# Motherboard_V2.net
KiCad netlist of a schematic drawn in EAGLE
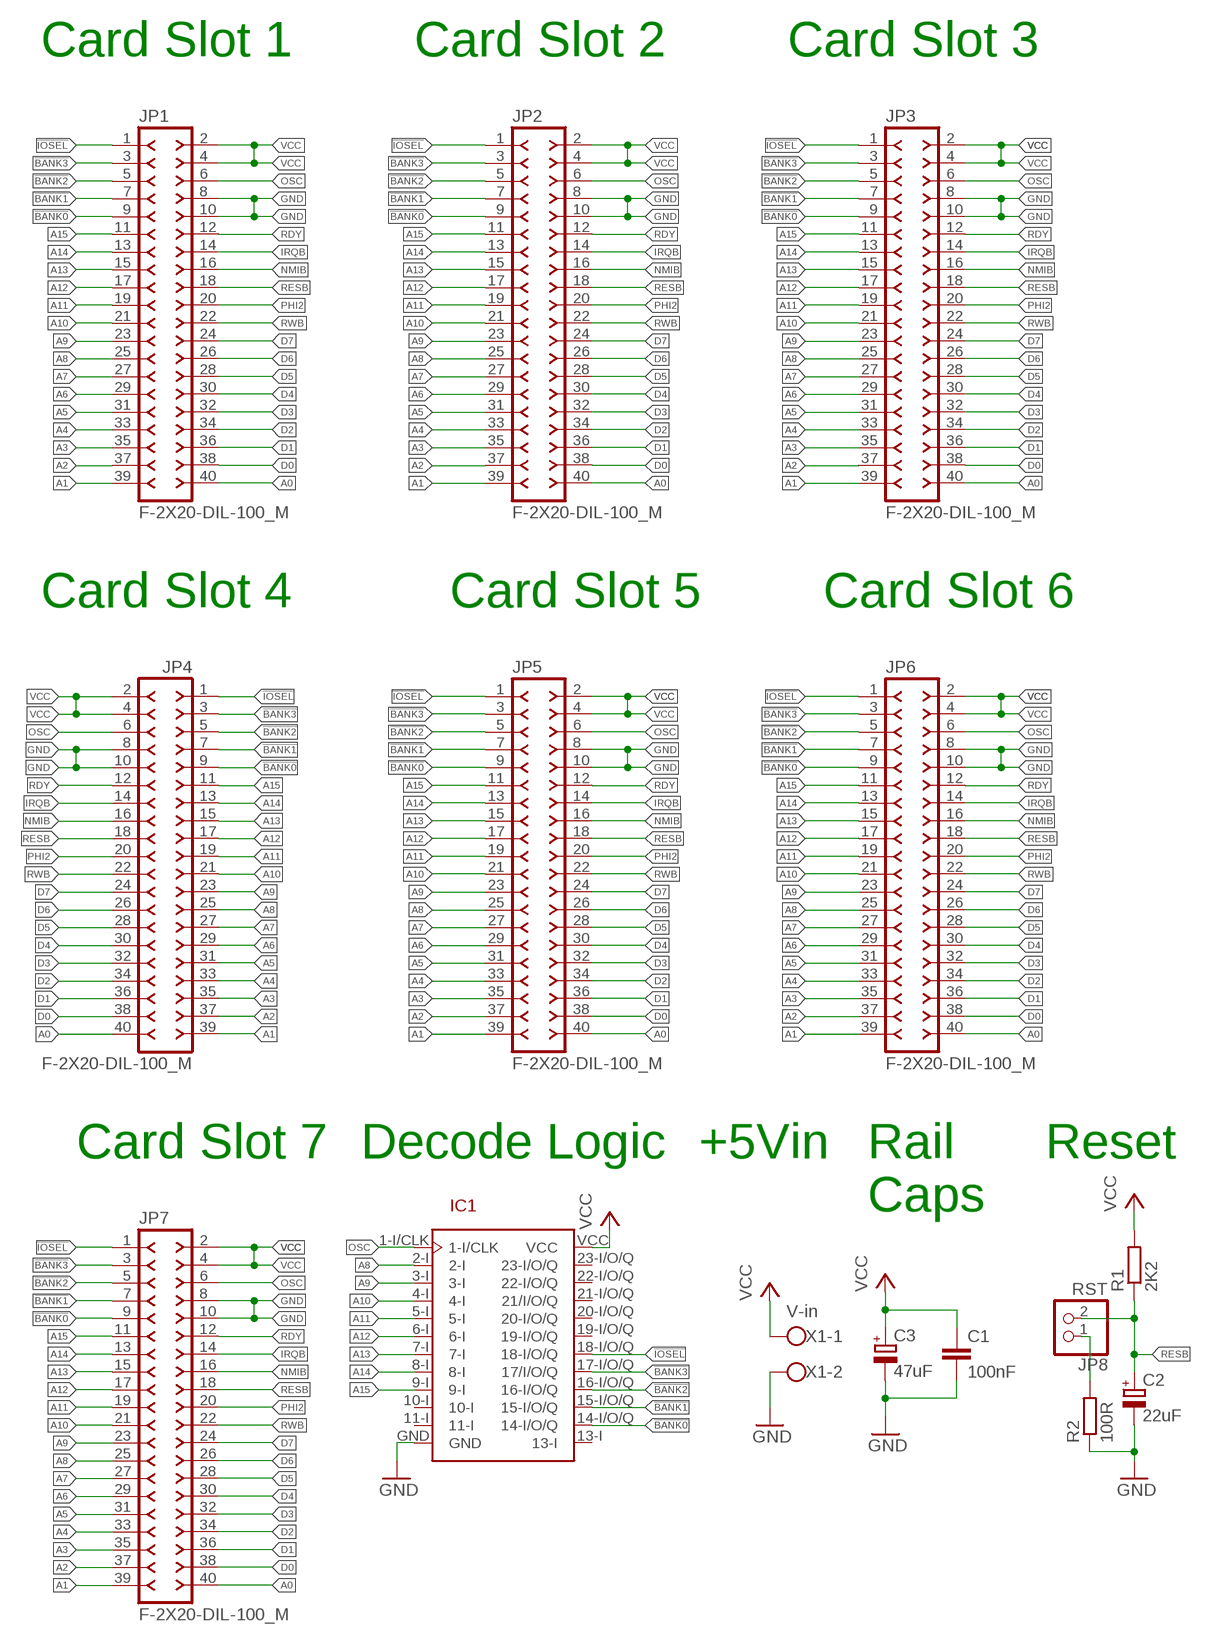
[diagram p0: schematic, sheet 1]

(export (version "E")
  (design (tool "Eeschema 10.0.6"))
  (components
    (comp (ref "C1")
      (value "100nF")
      (footprint "eagle-import:C050-025X075")
      (libsource (lib "eagle-import") (part "C-EU050-025X075"))
    )
    (comp (ref "C2")
      (value "22uF")
      (footprint "eagle-import:E2-5")
      (libsource (lib "eagle-import") (part "CPOL-EUE2-5"))
    )
    (comp (ref "C3")
      (value "47uF")
      (footprint "eagle-import:E2,5-7")
      (libsource (lib "eagle-import") (part "CPOL-EUE2.5-7"))
    )
    (comp (ref "IC1")
      (value "GAL22V10D-DIP")
      (footprint "eagle-import:DIP24")
      (libsource (lib "eagle-import") (part "GAL22V10D-DIP"))
    )
    (comp (ref "JP1")
      (value "F-2X20-DIL-100_M")
      (footprint "eagle-import:DIL-100-2X20_M")
      (libsource (lib "eagle-import") (part "F-2X20-DIL-100_M"))
    )
    (comp (ref "JP2")
      (value "F-2X20-DIL-100_M")
      (footprint "eagle-import:DIL-100-2X20_M")
      (libsource (lib "eagle-import") (part "F-2X20-DIL-100_M"))
    )
    (comp (ref "JP3")
      (value "F-2X20-DIL-100_M")
      (footprint "eagle-import:DIL-100-2X20_M")
      (libsource (lib "eagle-import") (part "F-2X20-DIL-100_M"))
    )
    (comp (ref "JP4")
      (value "F-2X20-DIL-100_M")
      (footprint "eagle-import:DIL-100-2X20_M")
      (libsource (lib "eagle-import") (part "F-2X20-DIL-100_M"))
    )
    (comp (ref "JP5")
      (value "F-2X20-DIL-100_M")
      (footprint "eagle-import:DIL-100-2X20_M")
      (libsource (lib "eagle-import") (part "F-2X20-DIL-100_M"))
    )
    (comp (ref "JP6")
      (value "F-2X20-DIL-100_M")
      (footprint "eagle-import:DIL-100-2X20_M")
      (libsource (lib "eagle-import") (part "F-2X20-DIL-100_M"))
    )
    (comp (ref "JP7")
      (value "F-2X20-DIL-100_M")
      (footprint "eagle-import:DIL-100-2X20_M")
      (libsource (lib "eagle-import") (part "F-2X20-DIL-100_M"))
    )
    (comp (ref "JP8")
      (value "RST")
      (footprint "eagle-import:1X02")
      (libsource (lib "eagle-import") (part "PINHD-1X2"))
    )
    (comp (ref "R1")
      (value "2K2")
      (footprint "eagle-import:0207_10")
      (libsource (lib "eagle-import") (part "R-EU_0207/10"))
    )
    (comp (ref "R2")
      (value "100R")
      (footprint "eagle-import:0207_10")
      (libsource (lib "eagle-import") (part "R-EU_0207/10"))
    )
    (comp (ref "X1")
      (value "V-in")
      (footprint "eagle-import:W237-102")
      (fields (field (name "MPN") "237-102"))
      (libsource (lib "eagle-import") (part "W237-102"))
    )
  )
  (nets
    (net (code "1") (name "/~{BANK0}") (class "Default")
      (node (ref "IC1") (pin "14-I/O/Q") (pinfunction "14-I/O/Q_14-I/O/Q") (pintype "bidirectional"))
      (node (ref "JP1") (pin "9") (pinfunction "9_9") (pintype "passive"))
      (node (ref "JP2") (pin "9") (pinfunction "9_9") (pintype "passive"))
      (node (ref "JP3") (pin "9") (pinfunction "9_9") (pintype "passive"))
      (node (ref "JP4") (pin "9") (pinfunction "9_9") (pintype "passive"))
      (node (ref "JP5") (pin "9") (pinfunction "9_9") (pintype "passive"))
      (node (ref "JP6") (pin "9") (pinfunction "9_9") (pintype "passive"))
      (node (ref "JP7") (pin "9") (pinfunction "9_9") (pintype "passive"))
    )
    (net (code "2") (name "/~{BANK1}") (class "Default")
      (node (ref "IC1") (pin "15-I/O/Q") (pinfunction "15-I/O/Q_15-I/O/Q") (pintype "bidirectional"))
      (node (ref "JP1") (pin "7") (pinfunction "7_7") (pintype "passive"))
      (node (ref "JP2") (pin "7") (pinfunction "7_7") (pintype "passive"))
      (node (ref "JP3") (pin "7") (pinfunction "7_7") (pintype "passive"))
      (node (ref "JP4") (pin "7") (pinfunction "7_7") (pintype "passive"))
      (node (ref "JP5") (pin "7") (pinfunction "7_7") (pintype "passive"))
      (node (ref "JP6") (pin "7") (pinfunction "7_7") (pintype "passive"))
      (node (ref "JP7") (pin "7") (pinfunction "7_7") (pintype "passive"))
    )
    (net (code "3") (name "/~{BANK2}") (class "Default")
      (node (ref "IC1") (pin "16-I/O/Q") (pinfunction "16-I/O/Q_16-I/O/Q") (pintype "bidirectional"))
      (node (ref "JP1") (pin "5") (pinfunction "5_5") (pintype "passive"))
      (node (ref "JP2") (pin "5") (pinfunction "5_5") (pintype "passive"))
      (node (ref "JP3") (pin "5") (pinfunction "5_5") (pintype "passive"))
      (node (ref "JP4") (pin "5") (pinfunction "5_5") (pintype "passive"))
      (node (ref "JP5") (pin "5") (pinfunction "5_5") (pintype "passive"))
      (node (ref "JP6") (pin "5") (pinfunction "5_5") (pintype "passive"))
      (node (ref "JP7") (pin "5") (pinfunction "5_5") (pintype "passive"))
    )
    (net (code "4") (name "/~{BANK3}") (class "Default")
      (node (ref "IC1") (pin "17-I/O/Q") (pinfunction "17/I/O/Q_17-I/O/Q") (pintype "bidirectional"))
      (node (ref "JP1") (pin "3") (pinfunction "3_3") (pintype "passive"))
      (node (ref "JP2") (pin "3") (pinfunction "3_3") (pintype "passive"))
      (node (ref "JP3") (pin "3") (pinfunction "3_3") (pintype "passive"))
      (node (ref "JP4") (pin "3") (pinfunction "3_3") (pintype "passive"))
      (node (ref "JP5") (pin "3") (pinfunction "3_3") (pintype "passive"))
      (node (ref "JP6") (pin "3") (pinfunction "3_3") (pintype "passive"))
      (node (ref "JP7") (pin "3") (pinfunction "3_3") (pintype "passive"))
    )
    (net (code "5") (name "/~{IOSEL}") (class "Default")
      (node (ref "IC1") (pin "18-I/O/Q") (pinfunction "18-I/O/Q_18-I/O/Q") (pintype "bidirectional"))
      (node (ref "JP1") (pin "1") (pinfunction "1_1") (pintype "passive"))
      (node (ref "JP2") (pin "1") (pinfunction "1_1") (pintype "passive"))
      (node (ref "JP3") (pin "1") (pinfunction "1_1") (pintype "passive"))
      (node (ref "JP4") (pin "1") (pinfunction "1_1") (pintype "passive"))
      (node (ref "JP5") (pin "1") (pinfunction "1_1") (pintype "passive"))
      (node (ref "JP6") (pin "1") (pinfunction "1_1") (pintype "passive"))
      (node (ref "JP7") (pin "1") (pinfunction "1_1") (pintype "passive"))
    )
    (net (code "6") (name "A0") (class "Default")
      (node (ref "JP1") (pin "40") (pinfunction "40_40") (pintype "passive"))
      (node (ref "JP2") (pin "40") (pinfunction "40_40") (pintype "passive"))
      (node (ref "JP3") (pin "40") (pinfunction "40_40") (pintype "passive"))
      (node (ref "JP4") (pin "40") (pinfunction "40_40") (pintype "passive"))
      (node (ref "JP5") (pin "40") (pinfunction "40_40") (pintype "passive"))
      (node (ref "JP6") (pin "40") (pinfunction "40_40") (pintype "passive"))
      (node (ref "JP7") (pin "40") (pinfunction "40_40") (pintype "passive"))
    )
    (net (code "7") (name "A1") (class "Default")
      (node (ref "JP1") (pin "39") (pinfunction "39_39") (pintype "passive"))
      (node (ref "JP2") (pin "39") (pinfunction "39_39") (pintype "passive"))
      (node (ref "JP3") (pin "39") (pinfunction "39_39") (pintype "passive"))
      (node (ref "JP4") (pin "39") (pinfunction "39_39") (pintype "passive"))
      (node (ref "JP5") (pin "39") (pinfunction "39_39") (pintype "passive"))
      (node (ref "JP6") (pin "39") (pinfunction "39_39") (pintype "passive"))
      (node (ref "JP7") (pin "39") (pinfunction "39_39") (pintype "passive"))
    )
    (net (code "8") (name "A2") (class "Default")
      (node (ref "JP1") (pin "37") (pinfunction "37_37") (pintype "passive"))
      (node (ref "JP2") (pin "37") (pinfunction "37_37") (pintype "passive"))
      (node (ref "JP3") (pin "37") (pinfunction "37_37") (pintype "passive"))
      (node (ref "JP4") (pin "37") (pinfunction "37_37") (pintype "passive"))
      (node (ref "JP5") (pin "37") (pinfunction "37_37") (pintype "passive"))
      (node (ref "JP6") (pin "37") (pinfunction "37_37") (pintype "passive"))
      (node (ref "JP7") (pin "37") (pinfunction "37_37") (pintype "passive"))
    )
    (net (code "9") (name "A3") (class "Default")
      (node (ref "JP1") (pin "35") (pinfunction "35_35") (pintype "passive"))
      (node (ref "JP2") (pin "35") (pinfunction "35_35") (pintype "passive"))
      (node (ref "JP3") (pin "35") (pinfunction "35_35") (pintype "passive"))
      (node (ref "JP4") (pin "35") (pinfunction "35_35") (pintype "passive"))
      (node (ref "JP5") (pin "35") (pinfunction "35_35") (pintype "passive"))
      (node (ref "JP6") (pin "35") (pinfunction "35_35") (pintype "passive"))
      (node (ref "JP7") (pin "35") (pinfunction "35_35") (pintype "passive"))
    )
    (net (code "10") (name "A4") (class "Default")
      (node (ref "JP1") (pin "33") (pinfunction "33_33") (pintype "passive"))
      (node (ref "JP2") (pin "33") (pinfunction "33_33") (pintype "passive"))
      (node (ref "JP3") (pin "33") (pinfunction "33_33") (pintype "passive"))
      (node (ref "JP4") (pin "33") (pinfunction "33_33") (pintype "passive"))
      (node (ref "JP5") (pin "33") (pinfunction "33_33") (pintype "passive"))
      (node (ref "JP6") (pin "33") (pinfunction "33_33") (pintype "passive"))
      (node (ref "JP7") (pin "33") (pinfunction "33_33") (pintype "passive"))
    )
    (net (code "11") (name "A5") (class "Default")
      (node (ref "JP1") (pin "31") (pinfunction "31_31") (pintype "passive"))
      (node (ref "JP2") (pin "31") (pinfunction "31_31") (pintype "passive"))
      (node (ref "JP3") (pin "31") (pinfunction "31_31") (pintype "passive"))
      (node (ref "JP4") (pin "31") (pinfunction "31_31") (pintype "passive"))
      (node (ref "JP5") (pin "31") (pinfunction "31_31") (pintype "passive"))
      (node (ref "JP6") (pin "31") (pinfunction "31_31") (pintype "passive"))
      (node (ref "JP7") (pin "31") (pinfunction "31_31") (pintype "passive"))
    )
    (net (code "12") (name "A6") (class "Default")
      (node (ref "JP1") (pin "29") (pinfunction "29_29") (pintype "passive"))
      (node (ref "JP2") (pin "29") (pinfunction "29_29") (pintype "passive"))
      (node (ref "JP3") (pin "29") (pinfunction "29_29") (pintype "passive"))
      (node (ref "JP4") (pin "29") (pinfunction "29_29") (pintype "passive"))
      (node (ref "JP5") (pin "29") (pinfunction "29_29") (pintype "passive"))
      (node (ref "JP6") (pin "29") (pinfunction "29_29") (pintype "passive"))
      (node (ref "JP7") (pin "29") (pinfunction "29_29") (pintype "passive"))
    )
    (net (code "13") (name "A7") (class "Default")
      (node (ref "JP1") (pin "27") (pinfunction "27_27") (pintype "passive"))
      (node (ref "JP2") (pin "27") (pinfunction "27_27") (pintype "passive"))
      (node (ref "JP3") (pin "27") (pinfunction "27_27") (pintype "passive"))
      (node (ref "JP4") (pin "27") (pinfunction "27_27") (pintype "passive"))
      (node (ref "JP5") (pin "27") (pinfunction "27_27") (pintype "passive"))
      (node (ref "JP6") (pin "27") (pinfunction "27_27") (pintype "passive"))
      (node (ref "JP7") (pin "27") (pinfunction "27_27") (pintype "passive"))
    )
    (net (code "14") (name "A8") (class "Default")
      (node (ref "IC1") (pin "2-I") (pinfunction "2-I_2-I") (pintype "input"))
      (node (ref "JP1") (pin "25") (pinfunction "25_25") (pintype "passive"))
      (node (ref "JP2") (pin "25") (pinfunction "25_25") (pintype "passive"))
      (node (ref "JP3") (pin "25") (pinfunction "25_25") (pintype "passive"))
      (node (ref "JP4") (pin "25") (pinfunction "25_25") (pintype "passive"))
      (node (ref "JP5") (pin "25") (pinfunction "25_25") (pintype "passive"))
      (node (ref "JP6") (pin "25") (pinfunction "25_25") (pintype "passive"))
      (node (ref "JP7") (pin "25") (pinfunction "25_25") (pintype "passive"))
    )
    (net (code "15") (name "A9") (class "Default")
      (node (ref "IC1") (pin "3-I") (pinfunction "3-I_3-I") (pintype "input"))
      (node (ref "JP1") (pin "23") (pinfunction "23_23") (pintype "passive"))
      (node (ref "JP2") (pin "23") (pinfunction "23_23") (pintype "passive"))
      (node (ref "JP3") (pin "23") (pinfunction "23_23") (pintype "passive"))
      (node (ref "JP4") (pin "23") (pinfunction "23_23") (pintype "passive"))
      (node (ref "JP5") (pin "23") (pinfunction "23_23") (pintype "passive"))
      (node (ref "JP6") (pin "23") (pinfunction "23_23") (pintype "passive"))
      (node (ref "JP7") (pin "23") (pinfunction "23_23") (pintype "passive"))
    )
    (net (code "16") (name "A10") (class "Default")
      (node (ref "IC1") (pin "4-I") (pinfunction "4-I_4-I") (pintype "input"))
      (node (ref "JP1") (pin "21") (pinfunction "21_21") (pintype "passive"))
      (node (ref "JP2") (pin "21") (pinfunction "21_21") (pintype "passive"))
      (node (ref "JP3") (pin "21") (pinfunction "21_21") (pintype "passive"))
      (node (ref "JP4") (pin "21") (pinfunction "21_21") (pintype "passive"))
      (node (ref "JP5") (pin "21") (pinfunction "21_21") (pintype "passive"))
      (node (ref "JP6") (pin "21") (pinfunction "21_21") (pintype "passive"))
      (node (ref "JP7") (pin "21") (pinfunction "21_21") (pintype "passive"))
    )
    (net (code "17") (name "A11") (class "Default")
      (node (ref "IC1") (pin "5-I") (pinfunction "5-I_5-I") (pintype "input"))
      (node (ref "JP1") (pin "19") (pinfunction "19_19") (pintype "passive"))
      (node (ref "JP2") (pin "19") (pinfunction "19_19") (pintype "passive"))
      (node (ref "JP3") (pin "19") (pinfunction "19_19") (pintype "passive"))
      (node (ref "JP4") (pin "19") (pinfunction "19_19") (pintype "passive"))
      (node (ref "JP5") (pin "19") (pinfunction "19_19") (pintype "passive"))
      (node (ref "JP6") (pin "19") (pinfunction "19_19") (pintype "passive"))
      (node (ref "JP7") (pin "19") (pinfunction "19_19") (pintype "passive"))
    )
    (net (code "18") (name "A12") (class "Default")
      (node (ref "IC1") (pin "6-I") (pinfunction "6-I_6-I") (pintype "input"))
      (node (ref "JP1") (pin "17") (pinfunction "17_17") (pintype "passive"))
      (node (ref "JP2") (pin "17") (pinfunction "17_17") (pintype "passive"))
      (node (ref "JP3") (pin "17") (pinfunction "17_17") (pintype "passive"))
      (node (ref "JP4") (pin "17") (pinfunction "17_17") (pintype "passive"))
      (node (ref "JP5") (pin "17") (pinfunction "17_17") (pintype "passive"))
      (node (ref "JP6") (pin "17") (pinfunction "17_17") (pintype "passive"))
      (node (ref "JP7") (pin "17") (pinfunction "17_17") (pintype "passive"))
    )
    (net (code "19") (name "A13") (class "Default")
      (node (ref "IC1") (pin "7-I") (pinfunction "7-I_7-I") (pintype "input"))
      (node (ref "JP1") (pin "15") (pinfunction "15_15") (pintype "passive"))
      (node (ref "JP2") (pin "15") (pinfunction "15_15") (pintype "passive"))
      (node (ref "JP3") (pin "15") (pinfunction "15_15") (pintype "passive"))
      (node (ref "JP4") (pin "15") (pinfunction "15_15") (pintype "passive"))
      (node (ref "JP5") (pin "15") (pinfunction "15_15") (pintype "passive"))
      (node (ref "JP6") (pin "15") (pinfunction "15_15") (pintype "passive"))
      (node (ref "JP7") (pin "15") (pinfunction "15_15") (pintype "passive"))
    )
    (net (code "20") (name "A14") (class "Default")
      (node (ref "IC1") (pin "8-I") (pinfunction "8-I_8-I") (pintype "input"))
      (node (ref "JP1") (pin "13") (pinfunction "13_13") (pintype "passive"))
      (node (ref "JP2") (pin "13") (pinfunction "13_13") (pintype "passive"))
      (node (ref "JP3") (pin "13") (pinfunction "13_13") (pintype "passive"))
      (node (ref "JP4") (pin "13") (pinfunction "13_13") (pintype "passive"))
      (node (ref "JP5") (pin "13") (pinfunction "13_13") (pintype "passive"))
      (node (ref "JP6") (pin "13") (pinfunction "13_13") (pintype "passive"))
      (node (ref "JP7") (pin "13") (pinfunction "13_13") (pintype "passive"))
    )
    (net (code "21") (name "A15") (class "Default")
      (node (ref "IC1") (pin "9-I") (pinfunction "9-I_9-I") (pintype "input"))
      (node (ref "JP1") (pin "11") (pinfunction "11_11") (pintype "passive"))
      (node (ref "JP2") (pin "11") (pinfunction "11_11") (pintype "passive"))
      (node (ref "JP3") (pin "11") (pinfunction "11_11") (pintype "passive"))
      (node (ref "JP4") (pin "11") (pinfunction "11_11") (pintype "passive"))
      (node (ref "JP5") (pin "11") (pinfunction "11_11") (pintype "passive"))
      (node (ref "JP6") (pin "11") (pinfunction "11_11") (pintype "passive"))
      (node (ref "JP7") (pin "11") (pinfunction "11_11") (pintype "passive"))
    )
    (net (code "22") (name "D0") (class "Default")
      (node (ref "JP1") (pin "38") (pinfunction "38_38") (pintype "passive"))
      (node (ref "JP2") (pin "38") (pinfunction "38_38") (pintype "passive"))
      (node (ref "JP3") (pin "38") (pinfunction "38_38") (pintype "passive"))
      (node (ref "JP4") (pin "38") (pinfunction "38_38") (pintype "passive"))
      (node (ref "JP5") (pin "38") (pinfunction "38_38") (pintype "passive"))
      (node (ref "JP6") (pin "38") (pinfunction "38_38") (pintype "passive"))
      (node (ref "JP7") (pin "38") (pinfunction "38_38") (pintype "passive"))
    )
    (net (code "23") (name "D1") (class "Default")
      (node (ref "JP1") (pin "36") (pinfunction "36_36") (pintype "passive"))
      (node (ref "JP2") (pin "36") (pinfunction "36_36") (pintype "passive"))
      (node (ref "JP3") (pin "36") (pinfunction "36_36") (pintype "passive"))
      (node (ref "JP4") (pin "36") (pinfunction "36_36") (pintype "passive"))
      (node (ref "JP5") (pin "36") (pinfunction "36_36") (pintype "passive"))
      (node (ref "JP6") (pin "36") (pinfunction "36_36") (pintype "passive"))
      (node (ref "JP7") (pin "36") (pinfunction "36_36") (pintype "passive"))
    )
    (net (code "24") (name "D2") (class "Default")
      (node (ref "JP1") (pin "34") (pinfunction "34_34") (pintype "passive"))
      (node (ref "JP2") (pin "34") (pinfunction "34_34") (pintype "passive"))
      (node (ref "JP3") (pin "34") (pinfunction "34_34") (pintype "passive"))
      (node (ref "JP4") (pin "34") (pinfunction "34_34") (pintype "passive"))
      (node (ref "JP5") (pin "34") (pinfunction "34_34") (pintype "passive"))
      (node (ref "JP6") (pin "34") (pinfunction "34_34") (pintype "passive"))
      (node (ref "JP7") (pin "34") (pinfunction "34_34") (pintype "passive"))
    )
    (net (code "25") (name "D3") (class "Default")
      (node (ref "JP1") (pin "32") (pinfunction "32_32") (pintype "passive"))
      (node (ref "JP2") (pin "32") (pinfunction "32_32") (pintype "passive"))
      (node (ref "JP3") (pin "32") (pinfunction "32_32") (pintype "passive"))
      (node (ref "JP4") (pin "32") (pinfunction "32_32") (pintype "passive"))
      (node (ref "JP5") (pin "32") (pinfunction "32_32") (pintype "passive"))
      (node (ref "JP6") (pin "32") (pinfunction "32_32") (pintype "passive"))
      (node (ref "JP7") (pin "32") (pinfunction "32_32") (pintype "passive"))
    )
    (net (code "26") (name "D4") (class "Default")
      (node (ref "JP1") (pin "30") (pinfunction "30_30") (pintype "passive"))
      (node (ref "JP2") (pin "30") (pinfunction "30_30") (pintype "passive"))
      (node (ref "JP3") (pin "30") (pinfunction "30_30") (pintype "passive"))
      (node (ref "JP4") (pin "30") (pinfunction "30_30") (pintype "passive"))
      (node (ref "JP5") (pin "30") (pinfunction "30_30") (pintype "passive"))
      (node (ref "JP6") (pin "30") (pinfunction "30_30") (pintype "passive"))
      (node (ref "JP7") (pin "30") (pinfunction "30_30") (pintype "passive"))
    )
    (net (code "27") (name "D5") (class "Default")
      (node (ref "JP1") (pin "28") (pinfunction "28_28") (pintype "passive"))
      (node (ref "JP2") (pin "28") (pinfunction "28_28") (pintype "passive"))
      (node (ref "JP3") (pin "28") (pinfunction "28_28") (pintype "passive"))
      (node (ref "JP4") (pin "28") (pinfunction "28_28") (pintype "passive"))
      (node (ref "JP5") (pin "28") (pinfunction "28_28") (pintype "passive"))
      (node (ref "JP6") (pin "28") (pinfunction "28_28") (pintype "passive"))
      (node (ref "JP7") (pin "28") (pinfunction "28_28") (pintype "passive"))
    )
    (net (code "28") (name "D6") (class "Default")
      (node (ref "JP1") (pin "26") (pinfunction "26_26") (pintype "passive"))
      (node (ref "JP2") (pin "26") (pinfunction "26_26") (pintype "passive"))
      (node (ref "JP3") (pin "26") (pinfunction "26_26") (pintype "passive"))
      (node (ref "JP4") (pin "26") (pinfunction "26_26") (pintype "passive"))
      (node (ref "JP5") (pin "26") (pinfunction "26_26") (pintype "passive"))
      (node (ref "JP6") (pin "26") (pinfunction "26_26") (pintype "passive"))
      (node (ref "JP7") (pin "26") (pinfunction "26_26") (pintype "passive"))
    )
    (net (code "29") (name "D7") (class "Default")
      (node (ref "JP1") (pin "24") (pinfunction "24_24") (pintype "passive"))
      (node (ref "JP2") (pin "24") (pinfunction "24_24") (pintype "passive"))
      (node (ref "JP3") (pin "24") (pinfunction "24_24") (pintype "passive"))
      (node (ref "JP4") (pin "24") (pinfunction "24_24") (pintype "passive"))
      (node (ref "JP5") (pin "24") (pinfunction "24_24") (pintype "passive"))
      (node (ref "JP6") (pin "24") (pinfunction "24_24") (pintype "passive"))
      (node (ref "JP7") (pin "24") (pinfunction "24_24") (pintype "passive"))
    )
    (net (code "30") (name "GND") (class "Default")
      (node (ref "C1") (pin "2") (pinfunction "2_2") (pintype "passive"))
      (node (ref "C2") (pin "-") (pinfunction "-_-") (pintype "passive"))
      (node (ref "C3") (pin "-") (pinfunction "-_-") (pintype "passive"))
      (node (ref "IC1") (pin "GND") (pinfunction "GND_GND") (pintype "power_in"))
      (node (ref "JP1") (pin "10") (pinfunction "10_10") (pintype "passive"))
      (node (ref "JP1") (pin "8") (pinfunction "8_8") (pintype "passive"))
      (node (ref "JP2") (pin "10") (pinfunction "10_10") (pintype "passive"))
      (node (ref "JP2") (pin "8") (pinfunction "8_8") (pintype "passive"))
      (node (ref "JP3") (pin "10") (pinfunction "10_10") (pintype "passive"))
      (node (ref "JP3") (pin "8") (pinfunction "8_8") (pintype "passive"))
      (node (ref "JP4") (pin "10") (pinfunction "10_10") (pintype "passive"))
      (node (ref "JP4") (pin "8") (pinfunction "8_8") (pintype "passive"))
      (node (ref "JP5") (pin "10") (pinfunction "10_10") (pintype "passive"))
      (node (ref "JP5") (pin "8") (pinfunction "8_8") (pintype "passive"))
      (node (ref "JP6") (pin "10") (pinfunction "10_10") (pintype "passive"))
      (node (ref "JP6") (pin "8") (pinfunction "8_8") (pintype "passive"))
      (node (ref "JP7") (pin "10") (pinfunction "10_10") (pintype "passive"))
      (node (ref "JP7") (pin "8") (pinfunction "8_8") (pintype "passive"))
      (node (ref "R2") (pin "1") (pinfunction "1_1") (pintype "passive"))
      (node (ref "X1") (pin "2") (pinfunction "KL_2") (pintype "passive"))
    )
    (net (code "31") (name "IRQB") (class "Default")
      (node (ref "JP1") (pin "14") (pinfunction "14_14") (pintype "passive"))
      (node (ref "JP2") (pin "14") (pinfunction "14_14") (pintype "passive"))
      (node (ref "JP3") (pin "14") (pinfunction "14_14") (pintype "passive"))
      (node (ref "JP4") (pin "14") (pinfunction "14_14") (pintype "passive"))
      (node (ref "JP5") (pin "14") (pinfunction "14_14") (pintype "passive"))
      (node (ref "JP6") (pin "14") (pinfunction "14_14") (pintype "passive"))
      (node (ref "JP7") (pin "14") (pinfunction "14_14") (pintype "passive"))
    )
    (net (code "32") (name "NMIB") (class "Default")
      (node (ref "JP1") (pin "16") (pinfunction "16_16") (pintype "passive"))
      (node (ref "JP2") (pin "16") (pinfunction "16_16") (pintype "passive"))
      (node (ref "JP3") (pin "16") (pinfunction "16_16") (pintype "passive"))
      (node (ref "JP4") (pin "16") (pinfunction "16_16") (pintype "passive"))
      (node (ref "JP5") (pin "16") (pinfunction "16_16") (pintype "passive"))
      (node (ref "JP6") (pin "16") (pinfunction "16_16") (pintype "passive"))
      (node (ref "JP7") (pin "16") (pinfunction "16_16") (pintype "passive"))
    )
    (net (code "33") (name "Net-(JP8-Pad1)") (class "Default")
      (node (ref "JP8") (pin "1") (pinfunction "1_1") (pintype "passive"))
      (node (ref "R2") (pin "2") (pinfunction "2_2") (pintype "passive"))
    )
    (net (code "34") (name "OSC") (class "Default")
      (node (ref "IC1") (pin "1-I/CLK") (pinfunction "1-I/CLK_1-I/CLK") (pintype "input"))
      (node (ref "JP1") (pin "6") (pinfunction "6_6") (pintype "passive"))
      (node (ref "JP2") (pin "6") (pinfunction "6_6") (pintype "passive"))
      (node (ref "JP3") (pin "6") (pinfunction "6_6") (pintype "passive"))
      (node (ref "JP4") (pin "6") (pinfunction "6_6") (pintype "passive"))
      (node (ref "JP5") (pin "6") (pinfunction "6_6") (pintype "passive"))
      (node (ref "JP6") (pin "6") (pinfunction "6_6") (pintype "passive"))
      (node (ref "JP7") (pin "6") (pinfunction "6_6") (pintype "passive"))
    )
    (net (code "35") (name "PHI2") (class "Default")
      (node (ref "JP1") (pin "20") (pinfunction "20_20") (pintype "passive"))
      (node (ref "JP2") (pin "20") (pinfunction "20_20") (pintype "passive"))
      (node (ref "JP3") (pin "20") (pinfunction "20_20") (pintype "passive"))
      (node (ref "JP4") (pin "20") (pinfunction "20_20") (pintype "passive"))
      (node (ref "JP5") (pin "20") (pinfunction "20_20") (pintype "passive"))
      (node (ref "JP6") (pin "20") (pinfunction "20_20") (pintype "passive"))
      (node (ref "JP7") (pin "20") (pinfunction "20_20") (pintype "passive"))
    )
    (net (code "36") (name "RDY") (class "Default")
      (node (ref "JP1") (pin "12") (pinfunction "12_12") (pintype "passive"))
      (node (ref "JP2") (pin "12") (pinfunction "12_12") (pintype "passive"))
      (node (ref "JP3") (pin "12") (pinfunction "12_12") (pintype "passive"))
      (node (ref "JP4") (pin "12") (pinfunction "12_12") (pintype "passive"))
      (node (ref "JP5") (pin "12") (pinfunction "12_12") (pintype "passive"))
      (node (ref "JP6") (pin "12") (pinfunction "12_12") (pintype "passive"))
      (node (ref "JP7") (pin "12") (pinfunction "12_12") (pintype "passive"))
    )
    (net (code "37") (name "RESB") (class "Default")
      (node (ref "C2") (pin "+") (pinfunction "+_+") (pintype "passive"))
      (node (ref "JP1") (pin "18") (pinfunction "18_18") (pintype "passive"))
      (node (ref "JP2") (pin "18") (pinfunction "18_18") (pintype "passive"))
      (node (ref "JP3") (pin "18") (pinfunction "18_18") (pintype "passive"))
      (node (ref "JP4") (pin "18") (pinfunction "18_18") (pintype "passive"))
      (node (ref "JP5") (pin "18") (pinfunction "18_18") (pintype "passive"))
      (node (ref "JP6") (pin "18") (pinfunction "18_18") (pintype "passive"))
      (node (ref "JP7") (pin "18") (pinfunction "18_18") (pintype "passive"))
      (node (ref "JP8") (pin "2") (pinfunction "2_2") (pintype "passive"))
      (node (ref "R1") (pin "1") (pinfunction "1_1") (pintype "passive"))
    )
    (net (code "38") (name "RWB") (class "Default")
      (node (ref "JP1") (pin "22") (pinfunction "22_22") (pintype "passive"))
      (node (ref "JP2") (pin "22") (pinfunction "22_22") (pintype "passive"))
      (node (ref "JP3") (pin "22") (pinfunction "22_22") (pintype "passive"))
      (node (ref "JP4") (pin "22") (pinfunction "22_22") (pintype "passive"))
      (node (ref "JP5") (pin "22") (pinfunction "22_22") (pintype "passive"))
      (node (ref "JP6") (pin "22") (pinfunction "22_22") (pintype "passive"))
      (node (ref "JP7") (pin "22") (pinfunction "22_22") (pintype "passive"))
    )
    (net (code "39") (name "VCC") (class "Default")
      (node (ref "C1") (pin "1") (pinfunction "1_1") (pintype "passive"))
      (node (ref "C3") (pin "+") (pinfunction "+_+") (pintype "passive"))
      (node (ref "IC1") (pin "VCC") (pinfunction "VCC_VCC") (pintype "power_in"))
      (node (ref "JP1") (pin "2") (pinfunction "2_2") (pintype "passive"))
      (node (ref "JP1") (pin "4") (pinfunction "4_4") (pintype "passive"))
      (node (ref "JP2") (pin "2") (pinfunction "2_2") (pintype "passive"))
      (node (ref "JP2") (pin "4") (pinfunction "4_4") (pintype "passive"))
      (node (ref "JP3") (pin "2") (pinfunction "2_2") (pintype "passive"))
      (node (ref "JP3") (pin "4") (pinfunction "4_4") (pintype "passive"))
      (node (ref "JP4") (pin "2") (pinfunction "2_2") (pintype "passive"))
      (node (ref "JP4") (pin "4") (pinfunction "4_4") (pintype "passive"))
      (node (ref "JP5") (pin "2") (pinfunction "2_2") (pintype "passive"))
      (node (ref "JP5") (pin "4") (pinfunction "4_4") (pintype "passive"))
      (node (ref "JP6") (pin "2") (pinfunction "2_2") (pintype "passive"))
      (node (ref "JP6") (pin "4") (pinfunction "4_4") (pintype "passive"))
      (node (ref "JP7") (pin "2") (pinfunction "2_2") (pintype "passive"))
      (node (ref "JP7") (pin "4") (pinfunction "4_4") (pintype "passive"))
      (node (ref "R1") (pin "2") (pinfunction "2_2") (pintype "passive"))
      (node (ref "X1") (pin "1") (pinfunction "KL_1") (pintype "passive"))
    )
    (net (code "40") (name "unconnected-(IC1-21{slash}I{slash}O{slash}Q-Pad21-I{slash}O{slash}Q)") (class "Default")
      (node (ref "IC1") (pin "21-I/O/Q") (pinfunction "21/I/O/Q_21-I/O/Q") (pintype "bidirectional"))
    )
    (net (code "41") (name "unconnected-(IC1-Pad10-I)") (class "Default")
      (node (ref "IC1") (pin "10-I") (pinfunction "10-I_10-I") (pintype "input"))
    )
    (net (code "42") (name "unconnected-(IC1-Pad11-I)") (class "Default")
      (node (ref "IC1") (pin "11-I") (pinfunction "11-I_11-I") (pintype "input"))
    )
    (net (code "43") (name "unconnected-(IC1-Pad13-I)") (class "Default")
      (node (ref "IC1") (pin "13-I") (pinfunction "13-I_13-I") (pintype "input"))
    )
    (net (code "44") (name "unconnected-(IC1-Pad19-I{slash}O{slash}Q)") (class "Default")
      (node (ref "IC1") (pin "19-I/O/Q") (pinfunction "19-I/O/Q_19-I/O/Q") (pintype "bidirectional"))
    )
    (net (code "45") (name "unconnected-(IC1-Pad20-I{slash}O{slash}Q)") (class "Default")
      (node (ref "IC1") (pin "20-I/O/Q") (pinfunction "20-I/O/Q_20-I/O/Q") (pintype "bidirectional"))
    )
    (net (code "46") (name "unconnected-(IC1-Pad22-I{slash}O{slash}Q)") (class "Default")
      (node (ref "IC1") (pin "22-I/O/Q") (pinfunction "22-I/O/Q_22-I/O/Q") (pintype "bidirectional"))
    )
    (net (code "47") (name "unconnected-(IC1-Pad23-I{slash}O{slash}Q)") (class "Default")
      (node (ref "IC1") (pin "23-I/O/Q") (pinfunction "23-I/O/Q_23-I/O/Q") (pintype "bidirectional"))
    )
  )
)
